# remote_2313_4313-1wire.net
KiCad netlist of a schematic drawn in EAGLE
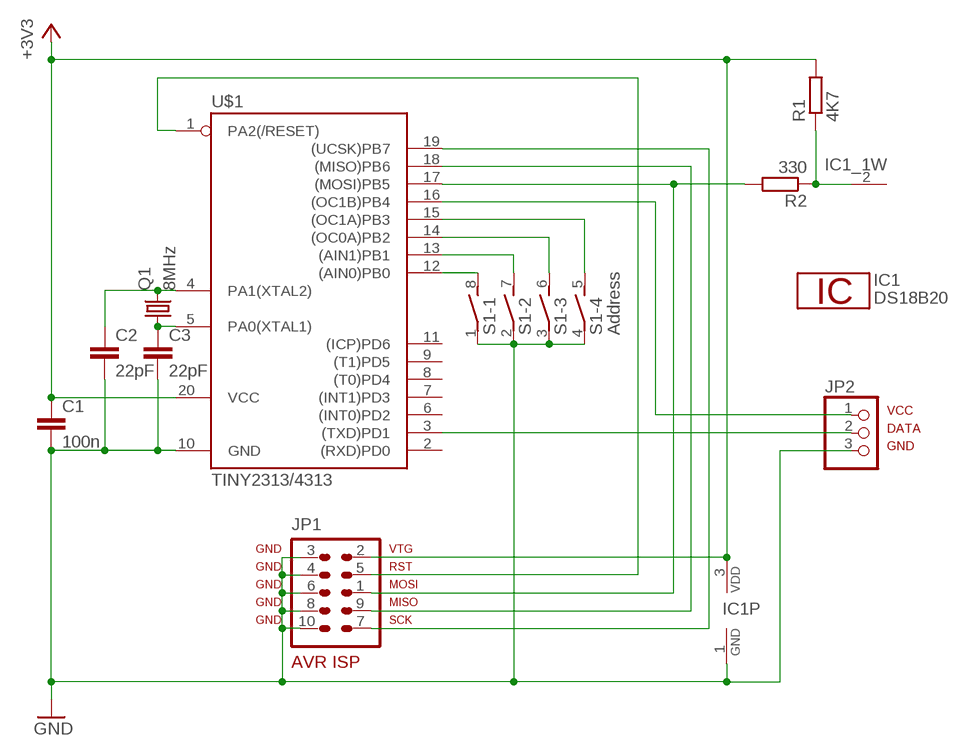
[diagram p0: schematic, sheet 1]

(export (version "E")
  (design (tool "Eeschema 10.0.6"))
  (components
    (comp (ref "C1")
      (value "100n")
      (footprint "eagle-import:C025-025X050")
      (libsource (lib "eagle-import") (part "C-EU025-025X050"))
    )
    (comp (ref "C2")
      (value "22pF")
      (footprint "eagle-import:C025-024X044")
      (libsource (lib "eagle-import") (part "C-EU025-024X044"))
    )
    (comp (ref "C3")
      (value "22pF")
      (footprint "eagle-import:C025-024X044")
      (libsource (lib "eagle-import") (part "C-EU025-024X044"))
    )
    (comp (ref "IC1")
      (value "DS18B20")
      (footprint "eagle-import:TO92-")
      (libsource (lib "eagle-import") (part "DS18B20"))
    )
    (comp (ref "JP1")
      (value "AVR-ISP-10")
      (footprint "eagle-import:AVR-ISP-10")
      (libsource (lib "eagle-import") (part "AVR-ISP-10"))
    )
    (comp (ref "JP2")
      (value "PINHD-1X3")
      (footprint "eagle-import:1X03")
      (libsource (lib "eagle-import") (part "PINHD-1X3"))
    )
    (comp (ref "Q1")
      (value "8MHz")
      (footprint "eagle-import:HC49U-V")
      (libsource (lib "eagle-import") (part "CRYSTALHC49U-V"))
    )
    (comp (ref "R1")
      (value "4K7")
      (footprint "eagle-import:0204_5")
      (libsource (lib "eagle-import") (part "R-EU_0204/5"))
    )
    (comp (ref "R2")
      (value "330")
      (footprint "eagle-import:0204_5")
      (libsource (lib "eagle-import") (part "R-EU_0204/5"))
    )
    (comp (ref "S1")
      (value "Address")
      (footprint "eagle-import:DIP04S")
      (libsource (lib "eagle-import") (part "DIP04S"))
    )
    (comp (ref "U$1")
      (value "TINY2313/4313")
      (footprint "eagle-import:DIL20")
      (libsource (lib "eagle-import") (part "TINY2313-P"))
    )
  )
  (nets
    (net (code "1") (name "+3V3") (class "Default")
      (node (ref "C1") (pin "1") (pinfunction "1_1") (pintype "passive"))
      (node (ref "IC1") (pin "3") (pinfunction "VDD_3") (pintype "power_in"))
      (node (ref "JP1") (pin "2") (pinfunction "2_2") (pintype "passive"))
      (node (ref "R1") (pin "2") (pinfunction "2_2") (pintype "passive"))
      (node (ref "U$1") (pin "20") (pinfunction "VCC_20") (pintype "power_in"))
    )
    (net (code "2") (name "GND") (class "Default")
      (node (ref "C1") (pin "2") (pinfunction "2_2") (pintype "passive"))
      (node (ref "C2") (pin "2") (pinfunction "2_2") (pintype "passive"))
      (node (ref "C3") (pin "2") (pinfunction "2_2") (pintype "passive"))
      (node (ref "IC1") (pin "1") (pinfunction "GND_1") (pintype "power_in"))
      (node (ref "JP1") (pin "10") (pinfunction "10_10") (pintype "passive"))
      (node (ref "JP1") (pin "3") (pinfunction "3_3") (pintype "passive"))
      (node (ref "JP1") (pin "4") (pinfunction "4_4") (pintype "passive"))
      (node (ref "JP1") (pin "6") (pinfunction "6_6") (pintype "passive"))
      (node (ref "JP1") (pin "8") (pinfunction "8_8") (pintype "passive"))
      (node (ref "JP2") (pin "3") (pinfunction "3_3") (pintype "passive"))
      (node (ref "S1") (pin "1") (pinfunction "1_1") (pintype "passive"))
      (node (ref "S1") (pin "2") (pinfunction "1_2") (pintype "passive"))
      (node (ref "S1") (pin "3") (pinfunction "1_3") (pintype "passive"))
      (node (ref "S1") (pin "4") (pinfunction "1_4") (pintype "passive"))
      (node (ref "U$1") (pin "10") (pinfunction "GND_10") (pintype "power_in"))
    )
    (net (code "3") (name "Net-(IC1C-1W)") (class "Default")
      (node (ref "IC1") (pin "2") (pinfunction "1W_2") (pintype "power_in"))
      (node (ref "R1") (pin "1") (pinfunction "1_1") (pintype "passive"))
      (node (ref "R2") (pin "1") (pinfunction "1_1") (pintype "passive"))
    )
    (net (code "4") (name "Net-(S1A-2)") (class "Default")
      (node (ref "S1") (pin "8") (pinfunction "2_8") (pintype "passive"))
      (node (ref "U$1") (pin "12") (pinfunction "(AIN0)PB0_12") (pintype "bidirectional"))
    )
    (net (code "5") (name "Net-(S1B-2)") (class "Default")
      (node (ref "S1") (pin "7") (pinfunction "2_7") (pintype "passive"))
      (node (ref "U$1") (pin "13") (pinfunction "(AIN1)PB1_13") (pintype "bidirectional"))
    )
    (net (code "6") (name "Net-(S1C-2)") (class "Default")
      (node (ref "S1") (pin "6") (pinfunction "2_6") (pintype "passive"))
      (node (ref "U$1") (pin "14") (pinfunction "(OC0A)PB2_14") (pintype "bidirectional"))
    )
    (net (code "7") (name "Net-(S1D-2)") (class "Default")
      (node (ref "S1") (pin "5") (pinfunction "2_5") (pintype "passive"))
      (node (ref "U$1") (pin "15") (pinfunction "(OC1A)PB3_15") (pintype "bidirectional"))
    )
    (net (code "8") (name "Net-(U$1-(MISO)PB6)") (class "Default")
      (node (ref "JP1") (pin "9") (pinfunction "9_9") (pintype "passive"))
      (node (ref "U$1") (pin "18") (pinfunction "(MISO)PB6_18") (pintype "bidirectional"))
    )
    (net (code "9") (name "Net-(U$1-(MOSI)PB5)") (class "Default")
      (node (ref "JP1") (pin "1") (pinfunction "1_1") (pintype "passive"))
      (node (ref "R2") (pin "2") (pinfunction "2_2") (pintype "passive"))
      (node (ref "U$1") (pin "17") (pinfunction "(MOSI)PB5_17") (pintype "bidirectional"))
    )
    (net (code "10") (name "Net-(U$1-(OC1B)PB4)") (class "Default")
      (node (ref "JP2") (pin "1") (pinfunction "1_1") (pintype "passive"))
      (node (ref "U$1") (pin "16") (pinfunction "(OC1B)PB4_16") (pintype "bidirectional"))
    )
    (net (code "11") (name "Net-(U$1-(TXD)PD1)") (class "Default")
      (node (ref "JP2") (pin "2") (pinfunction "2_2") (pintype "passive"))
      (node (ref "U$1") (pin "3") (pinfunction "(TXD)PD1_3") (pintype "bidirectional"))
    )
    (net (code "12") (name "Net-(U$1-(UCSK)PB7)") (class "Default")
      (node (ref "JP1") (pin "7") (pinfunction "7_7") (pintype "passive"))
      (node (ref "U$1") (pin "19") (pinfunction "(UCSK)PB7_19") (pintype "bidirectional"))
    )
    (net (code "13") (name "Net-(U$1-PA0(XTAL1))") (class "Default")
      (node (ref "C3") (pin "1") (pinfunction "1_1") (pintype "passive"))
      (node (ref "Q1") (pin "1") (pinfunction "1_1") (pintype "passive"))
      (node (ref "U$1") (pin "5") (pinfunction "PA0(XTAL1)_5") (pintype "bidirectional"))
    )
    (net (code "14") (name "Net-(U$1-PA1(XTAL2))") (class "Default")
      (node (ref "C2") (pin "1") (pinfunction "1_1") (pintype "passive"))
      (node (ref "Q1") (pin "2") (pinfunction "2_2") (pintype "passive"))
      (node (ref "U$1") (pin "4") (pinfunction "PA1(XTAL2)_4") (pintype "bidirectional"))
    )
    (net (code "15") (name "Net-(U$1-PA2({slash}RESET))") (class "Default")
      (node (ref "JP1") (pin "5") (pinfunction "5_5") (pintype "passive"))
      (node (ref "U$1") (pin "1") (pinfunction "PA2(/RESET)_1") (pintype "input"))
    )
    (net (code "16") (name "unconnected-(U$1-(ICP)PD6-Pad11)") (class "Default")
      (node (ref "U$1") (pin "11") (pinfunction "(ICP)PD6_11") (pintype "bidirectional"))
    )
    (net (code "17") (name "unconnected-(U$1-(INT0)PD2-Pad6)") (class "Default")
      (node (ref "U$1") (pin "6") (pinfunction "(INT0)PD2_6") (pintype "bidirectional"))
    )
    (net (code "18") (name "unconnected-(U$1-(INT1)PD3-Pad7)") (class "Default")
      (node (ref "U$1") (pin "7") (pinfunction "(INT1)PD3_7") (pintype "bidirectional"))
    )
    (net (code "19") (name "unconnected-(U$1-(RXD)PD0-Pad2)") (class "Default")
      (node (ref "U$1") (pin "2") (pinfunction "(RXD)PD0_2") (pintype "bidirectional"))
    )
    (net (code "20") (name "unconnected-(U$1-(T0)PD4-Pad8)") (class "Default")
      (node (ref "U$1") (pin "8") (pinfunction "(T0)PD4_8") (pintype "bidirectional"))
    )
    (net (code "21") (name "unconnected-(U$1-(T1)PD5-Pad9)") (class "Default")
      (node (ref "U$1") (pin "9") (pinfunction "(T1)PD5_9") (pintype "bidirectional"))
    )
  )
)
